# pcb1f.net
KiCad netlist of a schematic drawn in EAGLE
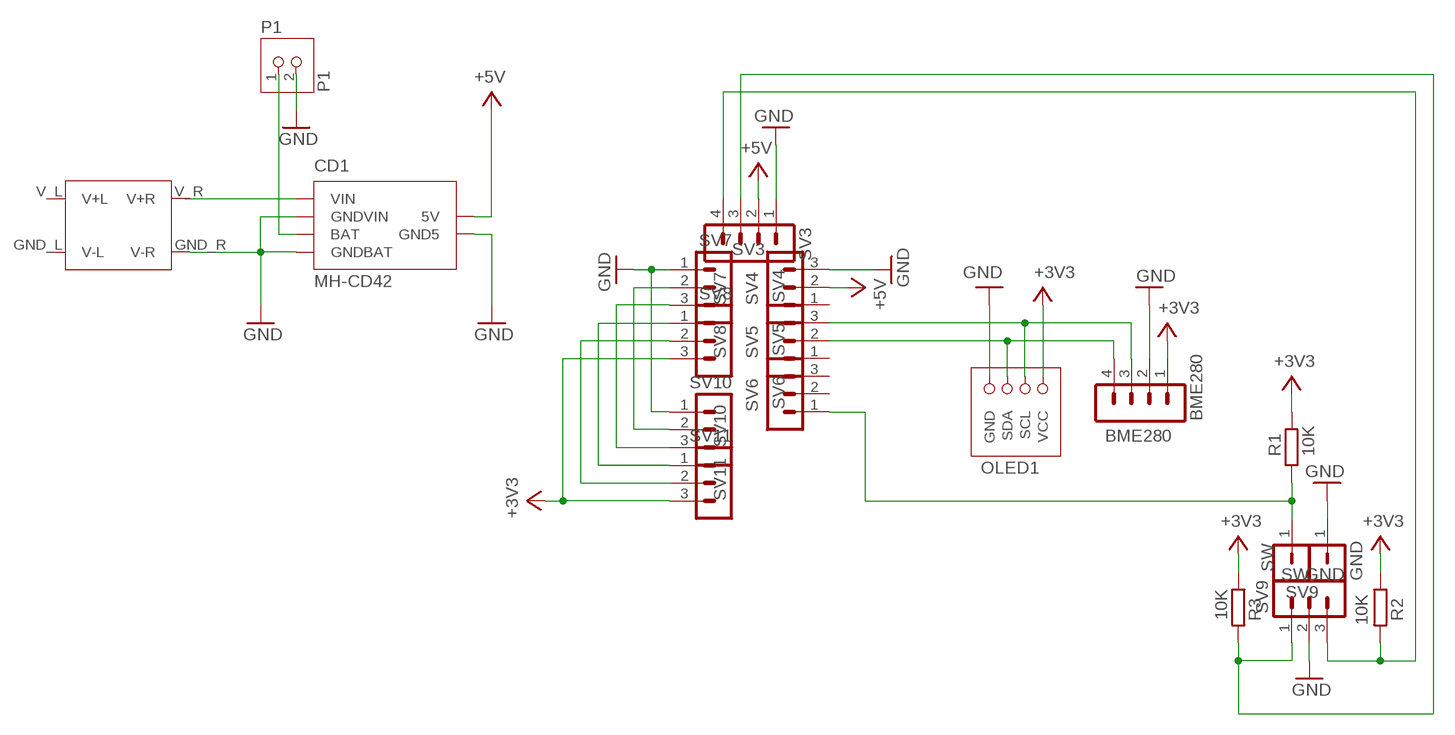
[diagram p0: schematic, sheet 1]

(export (version "E")
  (design (tool "Eeschema 10.0.6"))
  (components
    (comp (ref "BME280")
      (value "BME280")
      (footprint "eagle-import:PINHEAD-MA04-1")
      (libsource (lib "eagle-import") (part "PINHEAD-MA04-1"))
    )
    (comp (ref "CD1")
      (value "MH-CD42")
      (footprint "eagle-import:MH-CD42")
      (libsource (lib "eagle-import") (part "MH-CD42"))
    )
    (comp (ref "GND")
      (value "GND")
      (footprint "eagle-import:PINHEAD-MA01-1")
      (libsource (lib "eagle-import") (part "PINHEAD-MA01-1"))
    )
    (comp (ref "OLED1")
      (value "OLED-SSD1306-0.96")
      (footprint "eagle-import:OLED-I2C-0.96")
      (libsource (lib "eagle-import") (part "OLED-SSD1306-0.96"))
    )
    (comp (ref "P1")
      (value "P1")
      (footprint "eagle-import:JST-PH2")
      (libsource (lib "eagle-import") (part "JST-PH2"))
    )
    (comp (ref "R1")
      (value "10K")
      (footprint "eagle-import:0204_5")
      (libsource (lib "eagle-import") (part "R-EU_0204/5"))
    )
    (comp (ref "R2")
      (value "10K")
      (footprint "eagle-import:0204_5")
      (libsource (lib "eagle-import") (part "R-EU_0204/5"))
    )
    (comp (ref "R3")
      (value "10K")
      (footprint "eagle-import:0204_5")
      (libsource (lib "eagle-import") (part "R-EU_0204/5"))
    )
    (comp (ref "SV3")
      (value "SV3")
      (footprint "eagle-import:PINHEAD-MA04-1")
      (libsource (lib "eagle-import") (part "PINHEAD-MA04-1"))
    )
    (comp (ref "SV4")
      (value "SV4")
      (footprint "eagle-import:PINHEAD-MA03-1")
      (libsource (lib "eagle-import") (part "PINHEAD-MA03-1"))
    )
    (comp (ref "SV5")
      (value "SV5")
      (footprint "eagle-import:PINHEAD-MA03-1")
      (libsource (lib "eagle-import") (part "PINHEAD-MA03-1"))
    )
    (comp (ref "SV6")
      (value "SV6")
      (footprint "eagle-import:PINHEAD-MA03-1")
      (libsource (lib "eagle-import") (part "PINHEAD-MA03-1"))
    )
    (comp (ref "SV7")
      (value "SV7")
      (footprint "eagle-import:PINHEAD-MA03-1")
      (libsource (lib "eagle-import") (part "PINHEAD-MA03-1"))
    )
    (comp (ref "SV8")
      (value "SV8")
      (footprint "eagle-import:PINHEAD-MA03-1")
      (libsource (lib "eagle-import") (part "PINHEAD-MA03-1"))
    )
    (comp (ref "SV9")
      (value "SV9")
      (footprint "eagle-import:PINHEAD-MA03-1")
      (libsource (lib "eagle-import") (part "PINHEAD-MA03-1"))
    )
    (comp (ref "SV10")
      (value "SV10")
      (footprint "eagle-import:PINHEAD-MA03-1")
      (libsource (lib "eagle-import") (part "PINHEAD-MA03-1"))
    )
    (comp (ref "SV11")
      (value "SV11")
      (footprint "eagle-import:PINHEAD-MA03-1")
      (libsource (lib "eagle-import") (part "PINHEAD-MA03-1"))
    )
    (comp (ref "SW")
      (value "SW")
      (footprint "eagle-import:PINHEAD-MA01-1")
      (libsource (lib "eagle-import") (part "PINHEAD-MA01-1"))
    )
    (comp (ref "U$1")
      (value "AE-USB2.0-TYPE-C-CTRPB-1")
      (footprint "eagle-import:AE-USB2.0-TYPE-C-CTRPB-1")
      (libsource (lib "eagle-import") (part "AE-USB2.0-TYPE-C-CTRPB-1"))
    )
  )
  (nets
    (net (code "1") (name "+3V3") (class "Default")
      (node (ref "BME280") (pin "1") (pinfunction "1_1") (pintype "passive"))
      (node (ref "OLED1") (pin "VCC") (pinfunction "VCC_VCC") (pintype "bidirectional"))
      (node (ref "R1") (pin "2") (pinfunction "2_2") (pintype "passive"))
      (node (ref "R2") (pin "1") (pinfunction "1_1") (pintype "passive"))
      (node (ref "R3") (pin "1") (pinfunction "1_1") (pintype "passive"))
      (node (ref "SV11") (pin "3") (pinfunction "3_3") (pintype "passive"))
      (node (ref "SV8") (pin "3") (pinfunction "3_3") (pintype "passive"))
    )
    (net (code "2") (name "+5V") (class "Default")
      (node (ref "CD1") (pin "5V") (pinfunction "5V_5V") (pintype "bidirectional"))
      (node (ref "SV3") (pin "2") (pinfunction "2_2") (pintype "passive"))
      (node (ref "SV4") (pin "2") (pinfunction "2_2") (pintype "passive"))
    )
    (net (code "3") (name "GND") (class "Default")
      (node (ref "BME280") (pin "2") (pinfunction "2_2") (pintype "passive"))
      (node (ref "CD1") (pin "GND5V") (pinfunction "GND5_GND5V") (pintype "bidirectional"))
      (node (ref "CD1") (pin "GNDBAT") (pinfunction "GNDBAT_GNDBAT") (pintype "bidirectional"))
      (node (ref "CD1") (pin "GNDVIN") (pinfunction "GNDVIN_GNDVIN") (pintype "bidirectional"))
      (node (ref "GND") (pin "1") (pinfunction "1_1") (pintype "passive"))
      (node (ref "OLED1") (pin "GND") (pinfunction "GND_GND") (pintype "bidirectional"))
      (node (ref "P1") (pin "2") (pinfunction "2_2") (pintype "passive"))
      (node (ref "SV10") (pin "1") (pinfunction "1_1") (pintype "passive"))
      (node (ref "SV3") (pin "1") (pinfunction "1_1") (pintype "passive"))
      (node (ref "SV4") (pin "3") (pinfunction "3_3") (pintype "passive"))
      (node (ref "SV7") (pin "1") (pinfunction "1_1") (pintype "passive"))
      (node (ref "SV9") (pin "2") (pinfunction "2_2") (pintype "passive"))
      (node (ref "U$1") (pin "GND_R") (pinfunction "V-R_GND_R") (pintype "bidirectional"))
    )
    (net (code "4") (name "Net-(BME280-Pad3)") (class "Default")
      (node (ref "BME280") (pin "3") (pinfunction "3_3") (pintype "passive"))
      (node (ref "OLED1") (pin "SCL") (pinfunction "SCL_SCL") (pintype "bidirectional"))
      (node (ref "SV5") (pin "3") (pinfunction "3_3") (pintype "passive"))
    )
    (net (code "5") (name "Net-(BME280-Pad4)") (class "Default")
      (node (ref "BME280") (pin "4") (pinfunction "4_4") (pintype "passive"))
      (node (ref "OLED1") (pin "SDA") (pinfunction "SDA_SDA") (pintype "bidirectional"))
      (node (ref "SV5") (pin "2") (pinfunction "2_2") (pintype "passive"))
    )
    (net (code "6") (name "Net-(CD1-PadBAT)") (class "Default")
      (node (ref "CD1") (pin "BAT") (pinfunction "BAT_BAT") (pintype "bidirectional"))
      (node (ref "P1") (pin "1") (pinfunction "1_1") (pintype "passive"))
    )
    (net (code "7") (name "Net-(R1-Pad1)") (class "Default")
      (node (ref "R1") (pin "1") (pinfunction "1_1") (pintype "passive"))
      (node (ref "SV6") (pin "1") (pinfunction "1_1") (pintype "passive"))
      (node (ref "SW") (pin "1") (pinfunction "1_1") (pintype "passive"))
    )
    (net (code "8") (name "Net-(R2-Pad2)") (class "Default")
      (node (ref "R2") (pin "2") (pinfunction "2_2") (pintype "passive"))
      (node (ref "SV3") (pin "4") (pinfunction "4_4") (pintype "passive"))
      (node (ref "SV9") (pin "3") (pinfunction "3_3") (pintype "passive"))
    )
    (net (code "9") (name "Net-(R3-Pad2)") (class "Default")
      (node (ref "R3") (pin "2") (pinfunction "2_2") (pintype "passive"))
      (node (ref "SV3") (pin "3") (pinfunction "3_3") (pintype "passive"))
      (node (ref "SV9") (pin "1") (pinfunction "1_1") (pintype "passive"))
    )
    (net (code "10") (name "Net-(SV10-Pad2)") (class "Default")
      (node (ref "SV10") (pin "2") (pinfunction "2_2") (pintype "passive"))
      (node (ref "SV7") (pin "2") (pinfunction "2_2") (pintype "passive"))
    )
    (net (code "11") (name "Net-(SV10-Pad3)") (class "Default")
      (node (ref "SV10") (pin "3") (pinfunction "3_3") (pintype "passive"))
      (node (ref "SV7") (pin "3") (pinfunction "3_3") (pintype "passive"))
    )
    (net (code "12") (name "Net-(SV11-Pad1)") (class "Default")
      (node (ref "SV11") (pin "1") (pinfunction "1_1") (pintype "passive"))
      (node (ref "SV8") (pin "1") (pinfunction "1_1") (pintype "passive"))
    )
    (net (code "13") (name "Net-(SV11-Pad2)") (class "Default")
      (node (ref "SV11") (pin "2") (pinfunction "2_2") (pintype "passive"))
      (node (ref "SV8") (pin "2") (pinfunction "2_2") (pintype "passive"))
    )
    (net (code "14") (name "Net-(U$1-V+R)") (class "Default")
      (node (ref "CD1") (pin "VIN") (pinfunction "VIN_VIN") (pintype "bidirectional"))
      (node (ref "U$1") (pin "V_R") (pinfunction "V+R_V_R") (pintype "bidirectional"))
    )
    (net (code "15") (name "unconnected-(SV4-Pad1)") (class "Default")
      (node (ref "SV4") (pin "1") (pinfunction "1_1") (pintype "passive"))
    )
    (net (code "16") (name "unconnected-(SV5-Pad1)") (class "Default")
      (node (ref "SV5") (pin "1") (pinfunction "1_1") (pintype "passive"))
    )
    (net (code "17") (name "unconnected-(SV6-Pad2)") (class "Default")
      (node (ref "SV6") (pin "2") (pinfunction "2_2") (pintype "passive"))
    )
    (net (code "18") (name "unconnected-(SV6-Pad3)") (class "Default")
      (node (ref "SV6") (pin "3") (pinfunction "3_3") (pintype "passive"))
    )
    (net (code "19") (name "unconnected-(U$1-V+L-PadV_L)") (class "Default")
      (node (ref "U$1") (pin "V_L") (pinfunction "V+L_V_L") (pintype "bidirectional"))
    )
    (net (code "20") (name "unconnected-(U$1-V-L-PadGND_L)") (class "Default")
      (node (ref "U$1") (pin "GND_L") (pinfunction "V-L_GND_L") (pintype "bidirectional"))
    )
  )
)
